# BasicLED.net
KiCad netlist of a schematic drawn in EAGLE
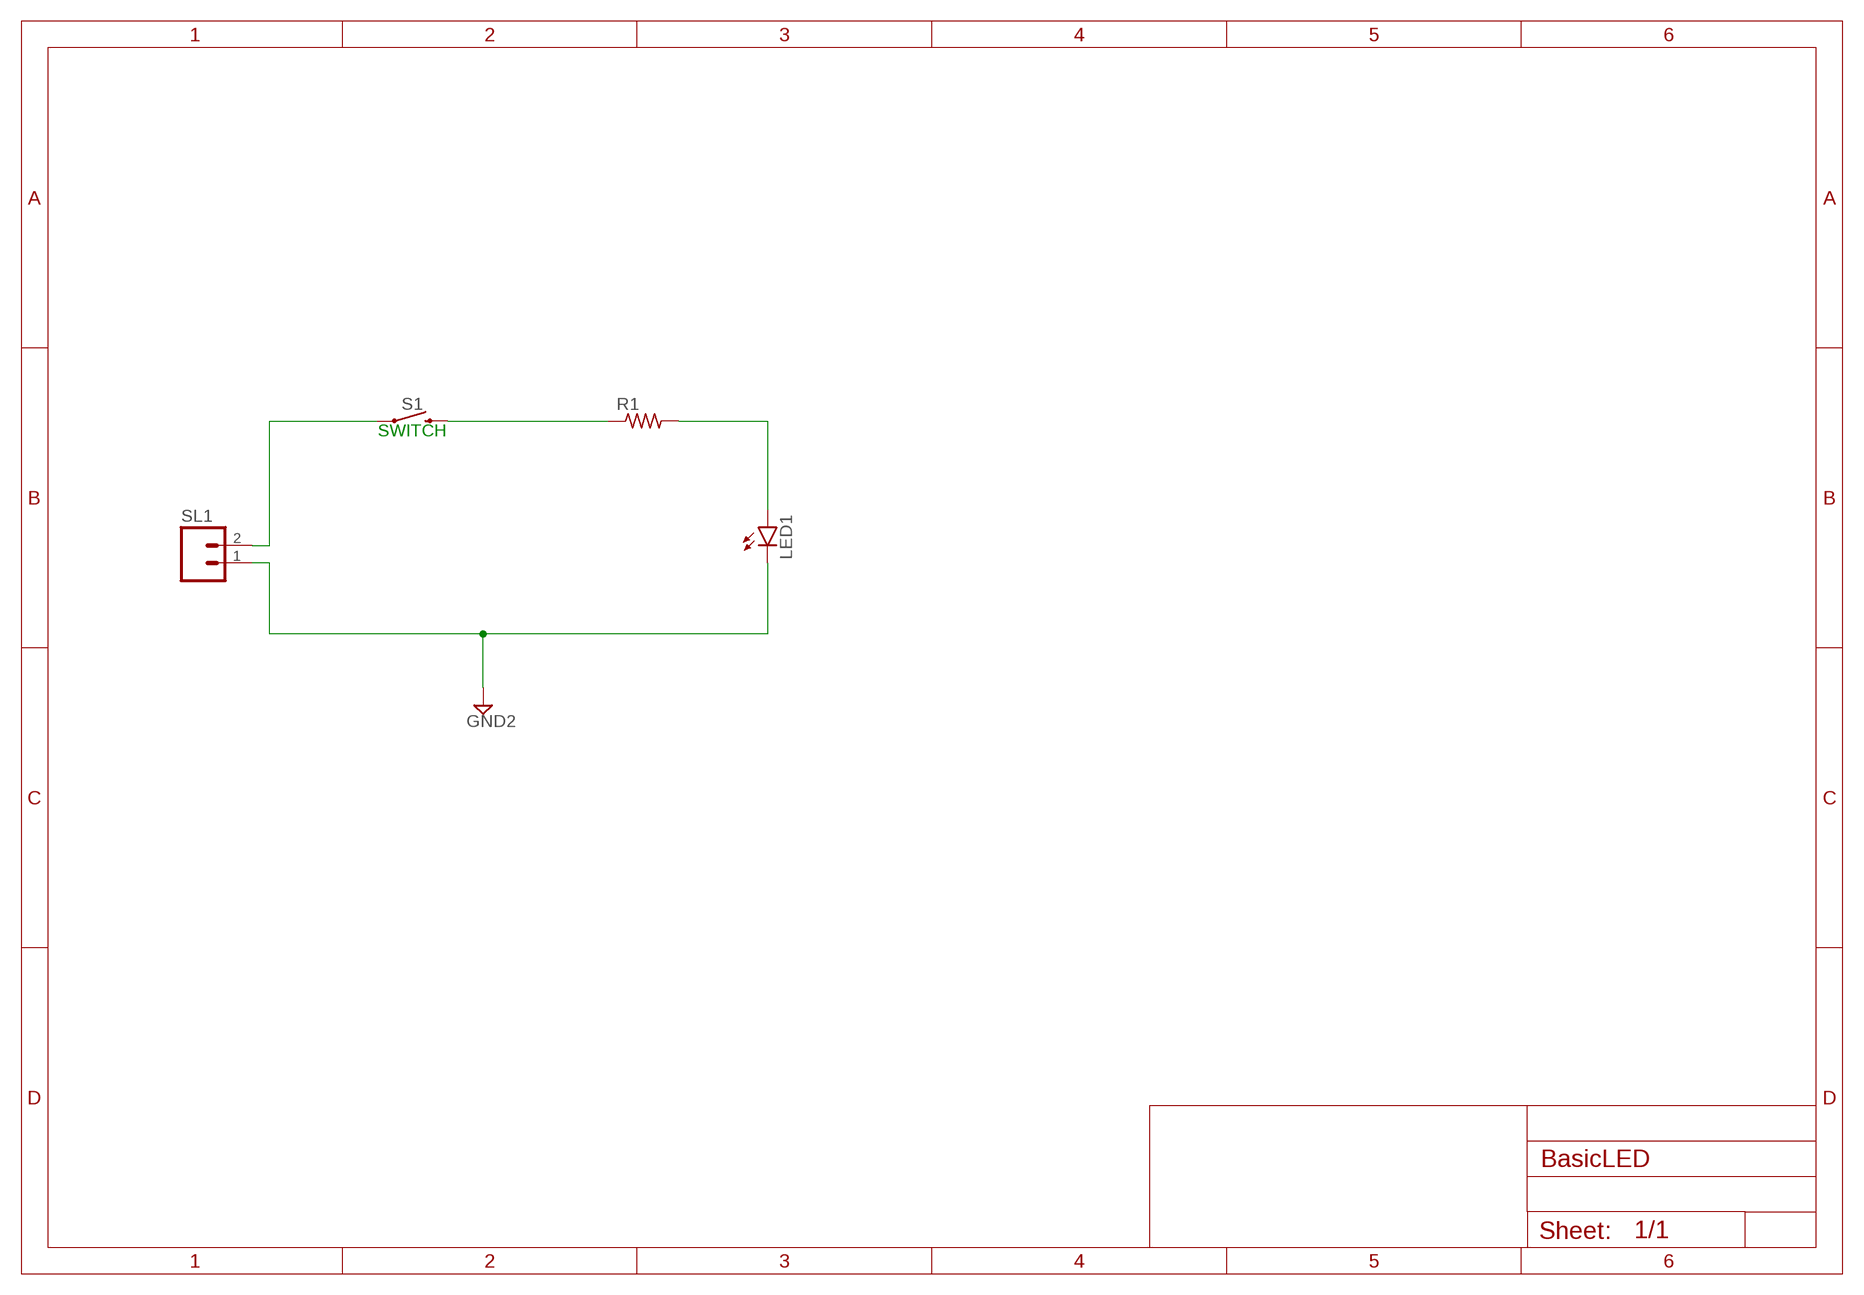
[diagram p0: schematic, sheet 1]

(export (version "E")
  (design (tool "Eeschema 10.0.6"))
  (components
    (comp (ref "LED1")
      (value "LEDCHIP-LED0805")
      (footprint "eagle-import:CHIP-LED0805")
      (libsource (lib "eagle-import") (part "LEDCHIP-LED0805"))
    )
    (comp (ref "R1")
      (value "R-US_R0805")
      (footprint "eagle-import:R0805")
      (libsource (lib "eagle-import") (part "R-US_R0805"))
    )
    (comp (ref "S1")
      (value "SWITCH")
      (footprint "eagle-import:TACTILE_SWITCH_SMD_4.5MM")
      (libsource (lib "eagle-import") (part "MOMENTARY-SWITCH-SPST-SMD-4.5MM"))
    )
    (comp (ref "SL1")
      (value "M02")
      (footprint "eagle-import:02P")
      (libsource (lib "eagle-import") (part "M02"))
    )
  )
  (nets
    (net (code "1") (name "GND2") (class "Default")
      (node (ref "LED1") (pin "C") (pinfunction "C_C") (pintype "passive"))
      (node (ref "SL1") (pin "1") (pinfunction "1_1") (pintype "passive"))
    )
    (net (code "2") (name "Net-(LED1-PadA)") (class "Default")
      (node (ref "LED1") (pin "A") (pinfunction "A_A") (pintype "passive"))
      (node (ref "R1") (pin "2") (pinfunction "2_2") (pintype "passive"))
    )
    (net (code "3") (name "Net-(R1-Pad1)") (class "Default")
      (node (ref "R1") (pin "1") (pinfunction "1_1") (pintype "passive"))
      (node (ref "S1") (pin "1") (pinfunction "2_1") (pintype "passive"))
      (node (ref "S1") (pin "4") (pinfunction "2_4") (pintype "passive"))
    )
    (net (code "4") (name "Net-(S1-1-Pad2)") (class "Default")
      (node (ref "S1") (pin "2") (pinfunction "1_2") (pintype "passive"))
      (node (ref "S1") (pin "3") (pinfunction "1_3") (pintype "passive"))
      (node (ref "SL1") (pin "2") (pinfunction "2_2") (pintype "passive"))
    )
  )
)
